# placa2caras_23.net
KiCad netlist of a schematic drawn in EAGLE
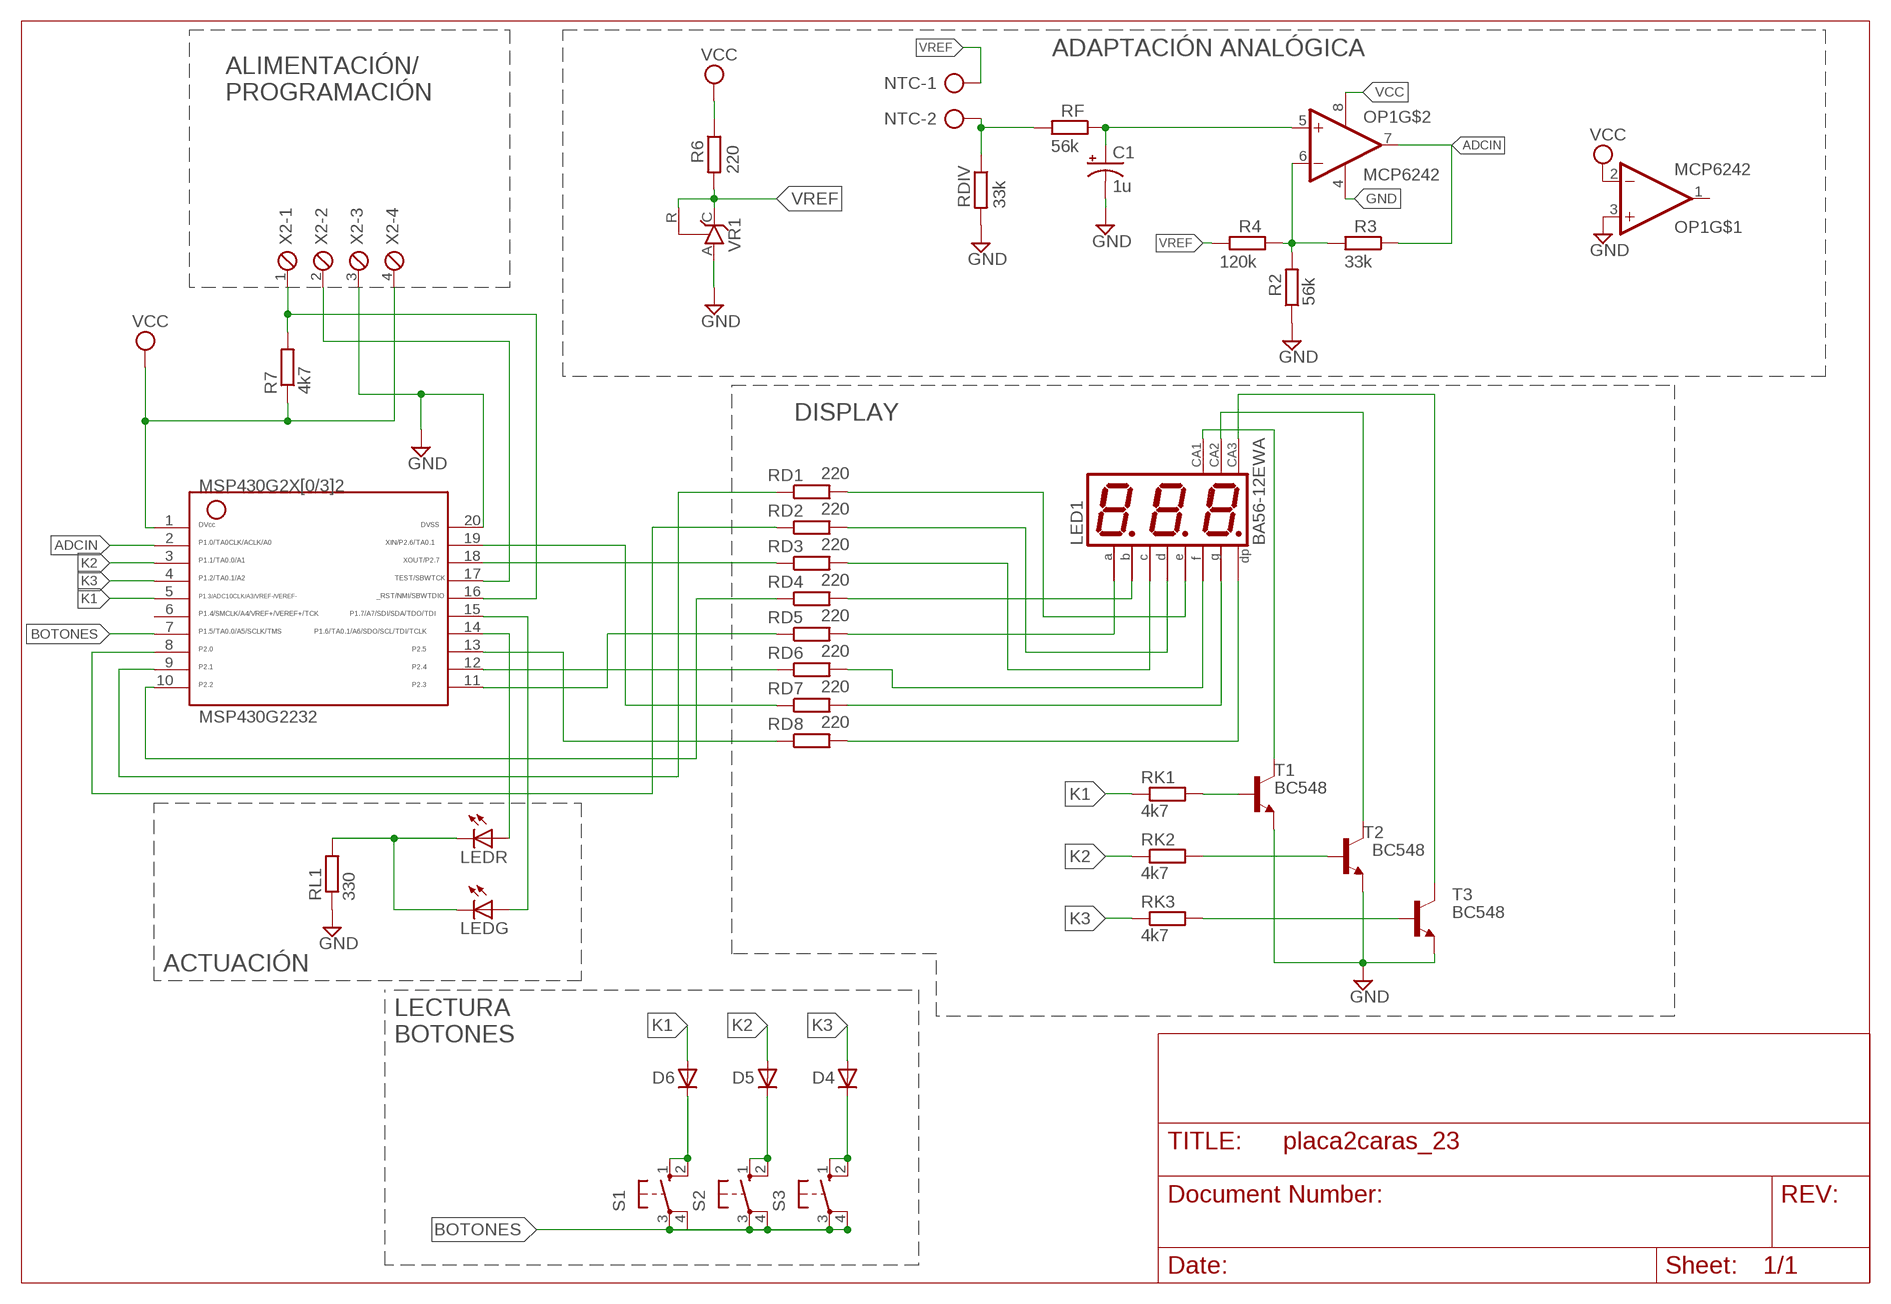
[diagram p0: schematic, sheet 1]

(export (version "E")
  (design (tool "Eeschema 10.0.6"))
  (components
    (comp (ref "C1")
      (value "1u")
      (footprint "eagle-import:E2,5-6E")
      (libsource (lib "eagle-import") (part "CPOL-USE2,5-6E"))
    )
    (comp (ref "D4")
      (value "1N4148DO35-10")
      (footprint "eagle-import:DO35-10")
      (libsource (lib "eagle-import") (part "1N4148DO35-10"))
    )
    (comp (ref "D5")
      (value "1N4148DO35-10")
      (footprint "eagle-import:DO35-10")
      (libsource (lib "eagle-import") (part "1N4148DO35-10"))
    )
    (comp (ref "D6")
      (value "1N4148DO35-10")
      (footprint "eagle-import:DO35-10")
      (libsource (lib "eagle-import") (part "1N4148DO35-10"))
    )
    (comp (ref "LED1")
      (value "BA56-12EWA")
      (footprint "eagle-import:BX56-12")
      (libsource (lib "eagle-import") (part "B?56-12WAAE"))
    )
    (comp (ref "LEDG")
      (value "LED5MM")
      (footprint "eagle-import:LED5MM")
      (libsource (lib "eagle-import") (part "LED5MM"))
    )
    (comp (ref "LEDR")
      (value "LED5MM")
      (footprint "eagle-import:LED5MM")
      (libsource (lib "eagle-import") (part "LED5MM"))
    )
    (comp (ref "MSP430G2232")
      (value "G2X[0/3]2---N20")
      (footprint "eagle-import:N20")
      (libsource (lib "eagle-import") (part "G2X[0/3]2---N20"))
    )
    (comp (ref "NTC")
      (value "AK500/2")
      (footprint "eagle-import:AK500_2")
      (libsource (lib "eagle-import") (part "AK500/2"))
    )
    (comp (ref "OP1")
      (value "MCP6242")
      (footprint "eagle-import:DIL8_MOD")
      (libsource (lib "eagle-import") (part "MCP6242CONPADGORDO"))
    )
    (comp (ref "R2")
      (value "56k")
      (footprint "eagle-import:0207_10")
      (libsource (lib "eagle-import") (part "R-EU_0207/10"))
    )
    (comp (ref "R3")
      (value "33k")
      (footprint "eagle-import:0207_10")
      (libsource (lib "eagle-import") (part "R-EU_0207/10"))
    )
    (comp (ref "R4")
      (value "120k")
      (footprint "eagle-import:0207_10")
      (libsource (lib "eagle-import") (part "R-EU_0207/10"))
    )
    (comp (ref "R6")
      (value "220")
      (footprint "eagle-import:0207_10")
      (libsource (lib "eagle-import") (part "R-EU_0207/10"))
    )
    (comp (ref "R7")
      (value "4k7")
      (footprint "eagle-import:0207_10")
      (libsource (lib "eagle-import") (part "R-EU_0207/10"))
    )
    (comp (ref "RD1")
      (value "220")
      (footprint "eagle-import:0207_10")
      (libsource (lib "eagle-import") (part "R-EU_0207/10"))
    )
    (comp (ref "RD2")
      (value "220")
      (footprint "eagle-import:0207_10")
      (libsource (lib "eagle-import") (part "R-EU_0207/10"))
    )
    (comp (ref "RD3")
      (value "220")
      (footprint "eagle-import:0207_10")
      (libsource (lib "eagle-import") (part "R-EU_0207/10"))
    )
    (comp (ref "RD4")
      (value "220")
      (footprint "eagle-import:0207_10")
      (libsource (lib "eagle-import") (part "R-EU_0207/10"))
    )
    (comp (ref "RD5")
      (value "220")
      (footprint "eagle-import:0207_10")
      (libsource (lib "eagle-import") (part "R-EU_0207/10"))
    )
    (comp (ref "RD6")
      (value "220")
      (footprint "eagle-import:0207_10")
      (libsource (lib "eagle-import") (part "R-EU_0207/10"))
    )
    (comp (ref "RD7")
      (value "220")
      (footprint "eagle-import:0207_10")
      (libsource (lib "eagle-import") (part "R-EU_0207/10"))
    )
    (comp (ref "RD8")
      (value "220")
      (footprint "eagle-import:0207_10")
      (libsource (lib "eagle-import") (part "R-EU_0207/10"))
    )
    (comp (ref "RDIV")
      (value "33k")
      (footprint "eagle-import:0207_10")
      (libsource (lib "eagle-import") (part "R-EU_0207/10"))
    )
    (comp (ref "RF")
      (value "56k")
      (footprint "eagle-import:0207_10")
      (libsource (lib "eagle-import") (part "R-EU_0207/10"))
    )
    (comp (ref "RK1")
      (value "4k7")
      (footprint "eagle-import:0207_10")
      (libsource (lib "eagle-import") (part "R-EU_0207/10"))
    )
    (comp (ref "RK2")
      (value "4k7")
      (footprint "eagle-import:0207_10")
      (libsource (lib "eagle-import") (part "R-EU_0207/10"))
    )
    (comp (ref "RK3")
      (value "4k7")
      (footprint "eagle-import:0207_10")
      (libsource (lib "eagle-import") (part "R-EU_0207/10"))
    )
    (comp (ref "RL1")
      (value "330")
      (footprint "eagle-import:0207_10")
      (libsource (lib "eagle-import") (part "R-EU_0207/10"))
    )
    (comp (ref "S1")
      (value "10-XX")
      (footprint "eagle-import:B3F-10XX")
      (fields (field (name "MPN") "B3F-1000"))
      (libsource (lib "eagle-import") (part "10-XX"))
    )
    (comp (ref "S2")
      (value "10-XX")
      (footprint "eagle-import:B3F-10XX")
      (fields (field (name "MPN") "B3F-1000"))
      (libsource (lib "eagle-import") (part "10-XX"))
    )
    (comp (ref "S3")
      (value "10-XX")
      (footprint "eagle-import:B3F-10XX")
      (fields (field (name "MPN") "B3F-1000"))
      (libsource (lib "eagle-import") (part "10-XX"))
    )
    (comp (ref "T1")
      (value "BC548")
      (footprint "eagle-import:TO92-EBC")
      (libsource (lib "eagle-import") (part "BC548"))
    )
    (comp (ref "T2")
      (value "BC548")
      (footprint "eagle-import:TO92-EBC")
      (libsource (lib "eagle-import") (part "BC548"))
    )
    (comp (ref "T3")
      (value "BC548")
      (footprint "eagle-import:TO92-EBC")
      (libsource (lib "eagle-import") (part "BC548"))
    )
    (comp (ref "VR1")
      (value "TL431CLP")
      (footprint "eagle-import:TO92-CLP")
      (libsource (lib "eagle-import") (part "TL431CLP"))
    )
    (comp (ref "X2")
      (value "MPT4")
      (footprint "eagle-import:4POL254")
      (libsource (lib "eagle-import") (part "MPT4"))
    )
  )
  (nets
    (net (code "1") (name "ADCIN") (class "Default")
      (node (ref "MSP430G2232") (pin "2") (pinfunction "2_2") (pintype "bidirectional"))
      (node (ref "OP1") (pin "7") (pinfunction "OUT_7") (pintype "output"))
      (node (ref "R3") (pin "1") (pinfunction "1_1") (pintype "passive"))
    )
    (net (code "2") (name "BOTONES") (class "Default")
      (node (ref "MSP430G2232") (pin "7") (pinfunction "7_7") (pintype "bidirectional"))
      (node (ref "S1") (pin "3") (pinfunction "P_3") (pintype "passive"))
      (node (ref "S1") (pin "4") (pinfunction "P1_4") (pintype "passive"))
      (node (ref "S2") (pin "3") (pinfunction "P_3") (pintype "passive"))
      (node (ref "S2") (pin "4") (pinfunction "P1_4") (pintype "passive"))
      (node (ref "S3") (pin "3") (pinfunction "P_3") (pintype "passive"))
      (node (ref "S3") (pin "4") (pinfunction "P1_4") (pintype "passive"))
    )
    (net (code "3") (name "GND") (class "Default")
      (node (ref "C1") (pin "-") (pinfunction "-_-") (pintype "passive"))
      (node (ref "MSP430G2232") (pin "20") (pinfunction "20_20") (pintype "bidirectional"))
      (node (ref "OP1") (pin "3") (pinfunction "+IN_3") (pintype "input"))
      (node (ref "OP1") (pin "4") (pinfunction "V-_4") (pintype "power_in"))
      (node (ref "R2") (pin "1") (pinfunction "1_1") (pintype "passive"))
      (node (ref "RDIV") (pin "2") (pinfunction "2_2") (pintype "passive"))
      (node (ref "RL1") (pin "1") (pinfunction "1_1") (pintype "passive"))
      (node (ref "T1") (pin "E") (pinfunction "E_E") (pintype "passive"))
      (node (ref "T2") (pin "E") (pinfunction "E_E") (pintype "passive"))
      (node (ref "T3") (pin "E") (pinfunction "E_E") (pintype "passive"))
      (node (ref "VR1") (pin "A") (pinfunction "A_A") (pintype "passive"))
      (node (ref "X2") (pin "3") (pinfunction "1_3") (pintype "passive"))
    )
    (net (code "4") (name "K1") (class "Default")
      (node (ref "D6") (pin "A") (pinfunction "A_A") (pintype "passive"))
      (node (ref "MSP430G2232") (pin "5") (pinfunction "5_5") (pintype "bidirectional"))
      (node (ref "RK1") (pin "1") (pinfunction "1_1") (pintype "passive"))
    )
    (net (code "5") (name "K2") (class "Default")
      (node (ref "D5") (pin "A") (pinfunction "A_A") (pintype "passive"))
      (node (ref "MSP430G2232") (pin "3") (pinfunction "3_3") (pintype "bidirectional"))
      (node (ref "RK2") (pin "1") (pinfunction "1_1") (pintype "passive"))
    )
    (net (code "6") (name "K3") (class "Default")
      (node (ref "D4") (pin "A") (pinfunction "A_A") (pintype "passive"))
      (node (ref "MSP430G2232") (pin "4") (pinfunction "4_4") (pintype "bidirectional"))
      (node (ref "RK3") (pin "1") (pinfunction "1_1") (pintype "passive"))
    )
    (net (code "7") (name "Net-(LED1-A)") (class "Default")
      (node (ref "LED1") (pin "11") (pinfunction "A_11") (pintype "passive"))
      (node (ref "RD5") (pin "2") (pinfunction "2_2") (pintype "passive"))
    )
    (net (code "8") (name "Net-(LED1-B)") (class "Default")
      (node (ref "LED1") (pin "7") (pinfunction "B_7") (pintype "passive"))
      (node (ref "RD4") (pin "2") (pinfunction "2_2") (pintype "passive"))
    )
    (net (code "9") (name "Net-(LED1-C)") (class "Default")
      (node (ref "LED1") (pin "4") (pinfunction "C_4") (pintype "passive"))
      (node (ref "RD3") (pin "2") (pinfunction "2_2") (pintype "passive"))
    )
    (net (code "10") (name "Net-(LED1-CA-Pad8)") (class "Default")
      (node (ref "LED1") (pin "8") (pinfunction "CA_8") (pintype "passive"))
      (node (ref "T3") (pin "C") (pinfunction "C_C") (pintype "passive"))
    )
    (net (code "11") (name "Net-(LED1-CA-Pad9)") (class "Default")
      (node (ref "LED1") (pin "9") (pinfunction "CA_9") (pintype "passive"))
      (node (ref "T2") (pin "C") (pinfunction "C_C") (pintype "passive"))
    )
    (net (code "12") (name "Net-(LED1-CA-Pad12)") (class "Default")
      (node (ref "LED1") (pin "12") (pinfunction "CA_12") (pintype "passive"))
      (node (ref "T1") (pin "C") (pinfunction "C_C") (pintype "passive"))
    )
    (net (code "13") (name "Net-(LED1-D)") (class "Default")
      (node (ref "LED1") (pin "2") (pinfunction "D_2") (pintype "passive"))
      (node (ref "RD2") (pin "2") (pinfunction "2_2") (pintype "passive"))
    )
    (net (code "14") (name "Net-(LED1-DP)") (class "Default")
      (node (ref "LED1") (pin "3") (pinfunction "DP_3") (pintype "passive"))
      (node (ref "RD8") (pin "2") (pinfunction "2_2") (pintype "passive"))
    )
    (net (code "15") (name "Net-(LED1-E)") (class "Default")
      (node (ref "LED1") (pin "1") (pinfunction "E_1") (pintype "passive"))
      (node (ref "RD1") (pin "2") (pinfunction "2_2") (pintype "passive"))
    )
    (net (code "16") (name "Net-(LED1-F)") (class "Default")
      (node (ref "LED1") (pin "10") (pinfunction "F_10") (pintype "passive"))
      (node (ref "RD6") (pin "2") (pinfunction "2_2") (pintype "passive"))
    )
    (net (code "17") (name "Net-(LED1-G)") (class "Default")
      (node (ref "LED1") (pin "5") (pinfunction "G_5") (pintype "passive"))
      (node (ref "RD7") (pin "2") (pinfunction "2_2") (pintype "passive"))
    )
    (net (code "18") (name "Net-(LEDG-C)") (class "Default")
      (node (ref "LEDG") (pin "K") (pinfunction "C_K") (pintype "passive"))
      (node (ref "LEDR") (pin "K") (pinfunction "C_K") (pintype "passive"))
      (node (ref "RL1") (pin "2") (pinfunction "2_2") (pintype "passive"))
    )
    (net (code "19") (name "Net-(LEDG-PadA)") (class "Default")
      (node (ref "LEDG") (pin "A") (pinfunction "A_A") (pintype "passive"))
      (node (ref "MSP430G2232") (pin "15") (pinfunction "15_15") (pintype "bidirectional"))
    )
    (net (code "20") (name "Net-(LEDR-PadA)") (class "Default")
      (node (ref "LEDR") (pin "A") (pinfunction "A_A") (pintype "passive"))
      (node (ref "MSP430G2232") (pin "14") (pinfunction "14_14") (pintype "bidirectional"))
    )
    (net (code "21") (name "Net-(MSP430G2232-Pad8)") (class "Default")
      (node (ref "MSP430G2232") (pin "8") (pinfunction "8_8") (pintype "bidirectional"))
      (node (ref "RD2") (pin "1") (pinfunction "1_1") (pintype "passive"))
    )
    (net (code "22") (name "Net-(MSP430G2232-Pad9)") (class "Default")
      (node (ref "MSP430G2232") (pin "9") (pinfunction "9_9") (pintype "bidirectional"))
      (node (ref "RD1") (pin "1") (pinfunction "1_1") (pintype "passive"))
    )
    (net (code "23") (name "Net-(MSP430G2232-Pad10)") (class "Default")
      (node (ref "MSP430G2232") (pin "10") (pinfunction "10_10") (pintype "bidirectional"))
      (node (ref "RD4") (pin "1") (pinfunction "1_1") (pintype "passive"))
    )
    (net (code "24") (name "Net-(MSP430G2232-Pad11)") (class "Default")
      (node (ref "MSP430G2232") (pin "11") (pinfunction "11_11") (pintype "bidirectional"))
      (node (ref "RD5") (pin "1") (pinfunction "1_1") (pintype "passive"))
    )
    (net (code "25") (name "Net-(MSP430G2232-Pad12)") (class "Default")
      (node (ref "MSP430G2232") (pin "12") (pinfunction "12_12") (pintype "bidirectional"))
      (node (ref "RD6") (pin "1") (pinfunction "1_1") (pintype "passive"))
    )
    (net (code "26") (name "Net-(MSP430G2232-Pad13)") (class "Default")
      (node (ref "MSP430G2232") (pin "13") (pinfunction "13_13") (pintype "bidirectional"))
      (node (ref "RD8") (pin "1") (pinfunction "1_1") (pintype "passive"))
    )
    (net (code "27") (name "Net-(MSP430G2232-Pad16)") (class "Default")
      (node (ref "MSP430G2232") (pin "16") (pinfunction "16_16") (pintype "bidirectional"))
      (node (ref "R7") (pin "2") (pinfunction "2_2") (pintype "passive"))
      (node (ref "X2") (pin "1") (pinfunction "1_1") (pintype "passive"))
    )
    (net (code "28") (name "Net-(MSP430G2232-Pad18)") (class "Default")
      (node (ref "MSP430G2232") (pin "18") (pinfunction "18_18") (pintype "bidirectional"))
      (node (ref "RD3") (pin "1") (pinfunction "1_1") (pintype "passive"))
    )
    (net (code "29") (name "Net-(MSP430G2232-Pad19)") (class "Default")
      (node (ref "MSP430G2232") (pin "19") (pinfunction "19_19") (pintype "bidirectional"))
      (node (ref "RD7") (pin "1") (pinfunction "1_1") (pintype "passive"))
    )
    (net (code "30") (name "Net-(NTCB-KL)") (class "Default")
      (node (ref "NTC") (pin "2") (pinfunction "KL_2") (pintype "passive"))
      (node (ref "RDIV") (pin "1") (pinfunction "1_1") (pintype "passive"))
      (node (ref "RF") (pin "2") (pinfunction "2_2") (pintype "passive"))
    )
    (net (code "31") (name "Net-(OP1B-+IN)") (class "Default")
      (node (ref "C1") (pin "+") (pinfunction "+_+") (pintype "passive"))
      (node (ref "OP1") (pin "5") (pinfunction "+IN_5") (pintype "input"))
      (node (ref "RF") (pin "1") (pinfunction "1_1") (pintype "passive"))
    )
    (net (code "32") (name "Net-(OP1B--IN)") (class "Default")
      (node (ref "OP1") (pin "6") (pinfunction "-IN_6") (pintype "input"))
      (node (ref "R2") (pin "2") (pinfunction "2_2") (pintype "passive"))
      (node (ref "R3") (pin "2") (pinfunction "2_2") (pintype "passive"))
      (node (ref "R4") (pin "2") (pinfunction "2_2") (pintype "passive"))
    )
    (net (code "33") (name "Net-(RK1-Pad2)") (class "Default")
      (node (ref "RK1") (pin "2") (pinfunction "2_2") (pintype "passive"))
      (node (ref "T1") (pin "B") (pinfunction "B_B") (pintype "passive"))
    )
    (net (code "34") (name "Net-(RK2-Pad2)") (class "Default")
      (node (ref "RK2") (pin "2") (pinfunction "2_2") (pintype "passive"))
      (node (ref "T2") (pin "B") (pinfunction "B_B") (pintype "passive"))
    )
    (net (code "35") (name "Net-(RK3-Pad2)") (class "Default")
      (node (ref "RK3") (pin "2") (pinfunction "2_2") (pintype "passive"))
      (node (ref "T3") (pin "B") (pinfunction "B_B") (pintype "passive"))
    )
    (net (code "36") (name "Net-(S1-S)") (class "Default")
      (node (ref "D6") (pin "C") (pinfunction "C_C") (pintype "passive"))
      (node (ref "S1") (pin "1") (pinfunction "S_1") (pintype "passive"))
      (node (ref "S1") (pin "2") (pinfunction "S1_2") (pintype "passive"))
    )
    (net (code "37") (name "Net-(S2-S)") (class "Default")
      (node (ref "D5") (pin "C") (pinfunction "C_C") (pintype "passive"))
      (node (ref "S2") (pin "1") (pinfunction "S_1") (pintype "passive"))
      (node (ref "S2") (pin "2") (pinfunction "S1_2") (pintype "passive"))
    )
    (net (code "38") (name "Net-(S3-S)") (class "Default")
      (node (ref "D4") (pin "C") (pinfunction "C_C") (pintype "passive"))
      (node (ref "S3") (pin "1") (pinfunction "S_1") (pintype "passive"))
      (node (ref "S3") (pin "2") (pinfunction "S1_2") (pintype "passive"))
    )
    (net (code "39") (name "Net-(X2B-1)") (class "Default")
      (node (ref "MSP430G2232") (pin "17") (pinfunction "17_17") (pintype "bidirectional"))
      (node (ref "X2") (pin "2") (pinfunction "1_2") (pintype "passive"))
    )
    (net (code "40") (name "VCC") (class "Default")
      (node (ref "MSP430G2232") (pin "1") (pinfunction "1_1") (pintype "bidirectional"))
      (node (ref "OP1") (pin "2") (pinfunction "-IN_2") (pintype "input"))
      (node (ref "OP1") (pin "8") (pinfunction "V+_8") (pintype "power_in"))
      (node (ref "R6") (pin "1") (pinfunction "1_1") (pintype "passive"))
      (node (ref "R7") (pin "1") (pinfunction "1_1") (pintype "passive"))
      (node (ref "X2") (pin "4") (pinfunction "1_4") (pintype "passive"))
    )
    (net (code "41") (name "VREF") (class "Default")
      (node (ref "NTC") (pin "1") (pinfunction "KL_1") (pintype "passive"))
      (node (ref "R4") (pin "1") (pinfunction "1_1") (pintype "passive"))
      (node (ref "R6") (pin "2") (pinfunction "2_2") (pintype "passive"))
      (node (ref "VR1") (pin "C") (pinfunction "C_C") (pintype "passive"))
      (node (ref "VR1") (pin "R") (pinfunction "R_R") (pintype "passive"))
    )
    (net (code "42") (name "unconnected-(MSP430G2232-Pad6)") (class "Default")
      (node (ref "MSP430G2232") (pin "6") (pinfunction "6_6") (pintype "bidirectional"))
    )
    (net (code "43") (name "unconnected-(OP1A-OUT-Pad1)") (class "Default")
      (node (ref "OP1") (pin "1") (pinfunction "OUT_1") (pintype "output"))
    )
  )
)
